# schematic.net
KiCad netlist of a schematic drawn in EAGLE
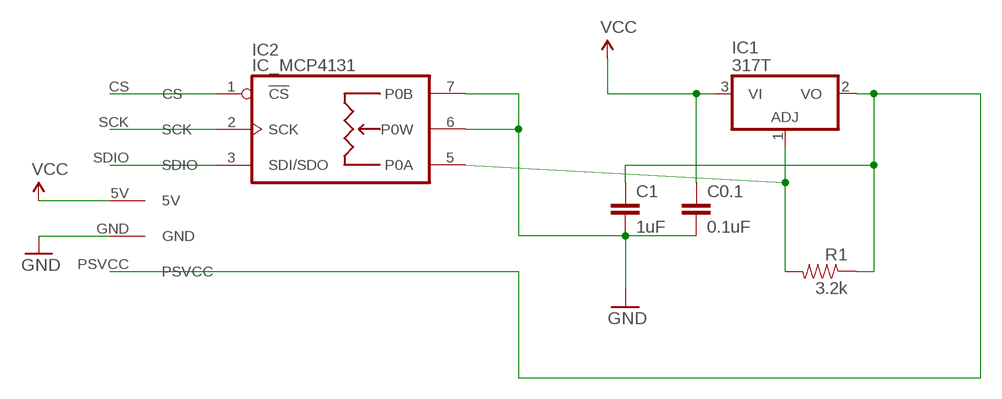
[diagram p0: schematic, sheet 1]

(export (version "E")
  (design (tool "Eeschema 10.0.6"))
  (components
    (comp (ref "C0.1")
      (value "0.1uF")
      (footprint "eagle-import:CAP-PTH-SMALL-KIT")
      (libsource (lib "eagle-import") (part "0.1UF-50V-20%(PTH)KIT-EZ"))
    )
    (comp (ref "C1")
      (value "1uF")
      (footprint "eagle-import:CAP-PTH-SMALL-KIT")
      (libsource (lib "eagle-import") (part "0.1UF-50V-20%(PTH)KIT-EZ"))
    )
    (comp (ref "IC1")
      (value "317T")
      (footprint "eagle-import:TO220H")
      (libsource (lib "eagle-import") (part "317T"))
    )
    (comp (ref "IC2")
      (value "IC_MCP4131")
      (footprint "eagle-import:DIP8")
      (libsource (lib "eagle-import") (part "IC_MCP4131"))
    )
    (comp (ref "R1")
      (value "3.2k")
      (footprint "eagle-import:AXIAL-0.3")
      (libsource (lib "eagle-import") (part "RESISTORAXIAL-0.3"))
    )
    (comp (ref "U$1")
      (value "PS_CONNNORMAL")
      (footprint "eagle-import:PS_CONN")
      (libsource (lib "eagle-import") (part "PS_CONNNORMAL"))
    )
  )
  (nets
    (net (code "1") (name "GND") (class "Default")
      (node (ref "C0.1") (pin "2") (pinfunction "2_2") (pintype "passive"))
      (node (ref "C1") (pin "2") (pinfunction "2_2") (pintype "passive"))
      (node (ref "IC2") (pin "6") (pinfunction "P0W_6") (pintype "passive"))
      (node (ref "IC2") (pin "7") (pinfunction "P0B_7") (pintype "passive"))
      (node (ref "U$1") (pin "GND") (pinfunction "GND_GND") (pintype "power_in"))
    )
    (net (code "2") (name "Net-(IC1-ADJ)") (class "Default")
      (node (ref "IC1") (pin "1") (pinfunction "ADJ_1") (pintype "input"))
      (node (ref "IC2") (pin "5") (pinfunction "P0A_5") (pintype "passive"))
      (node (ref "R1") (pin "P$2") (pinfunction "2_P$2") (pintype "passive"))
    )
    (net (code "3") (name "Net-(IC1-VO)") (class "Default")
      (node (ref "C1") (pin "1") (pinfunction "1_1") (pintype "passive"))
      (node (ref "IC1") (pin "2") (pinfunction "VO_2") (pintype "passive"))
      (node (ref "R1") (pin "P$1") (pinfunction "1_P$1") (pintype "passive"))
      (node (ref "U$1") (pin "PSVCC") (pinfunction "PSVCC_PSVCC") (pintype "power_in"))
    )
    (net (code "4") (name "Net-(IC2A-SCK)") (class "Default")
      (node (ref "IC2") (pin "2") (pinfunction "SCK_2") (pintype "input"))
      (node (ref "U$1") (pin "SCK") (pinfunction "SCK_SCK") (pintype "bidirectional"))
    )
    (net (code "5") (name "Net-(IC2A-SDI{slash}SDO)") (class "Default")
      (node (ref "IC2") (pin "3") (pinfunction "SDI/SDO_3") (pintype "bidirectional"))
      (node (ref "U$1") (pin "SDIO") (pinfunction "SDIO_SDIO") (pintype "bidirectional"))
    )
    (net (code "6") (name "Net-(IC2A-~{CS})") (class "Default")
      (node (ref "IC2") (pin "1") (pinfunction "~{CS}_1") (pintype "input"))
      (node (ref "U$1") (pin "CS") (pinfunction "CS_CS") (pintype "bidirectional"))
    )
    (net (code "7") (name "VCC") (class "Default")
      (node (ref "C0.1") (pin "1") (pinfunction "1_1") (pintype "passive"))
      (node (ref "IC1") (pin "3") (pinfunction "VI_3") (pintype "input"))
      (node (ref "U$1") (pin "5V") (pinfunction "5V_5V") (pintype "power_in"))
    )
  )
)
